# BATTERY_GESTION.net
KiCad netlist of a schematic drawn in Altium Designer
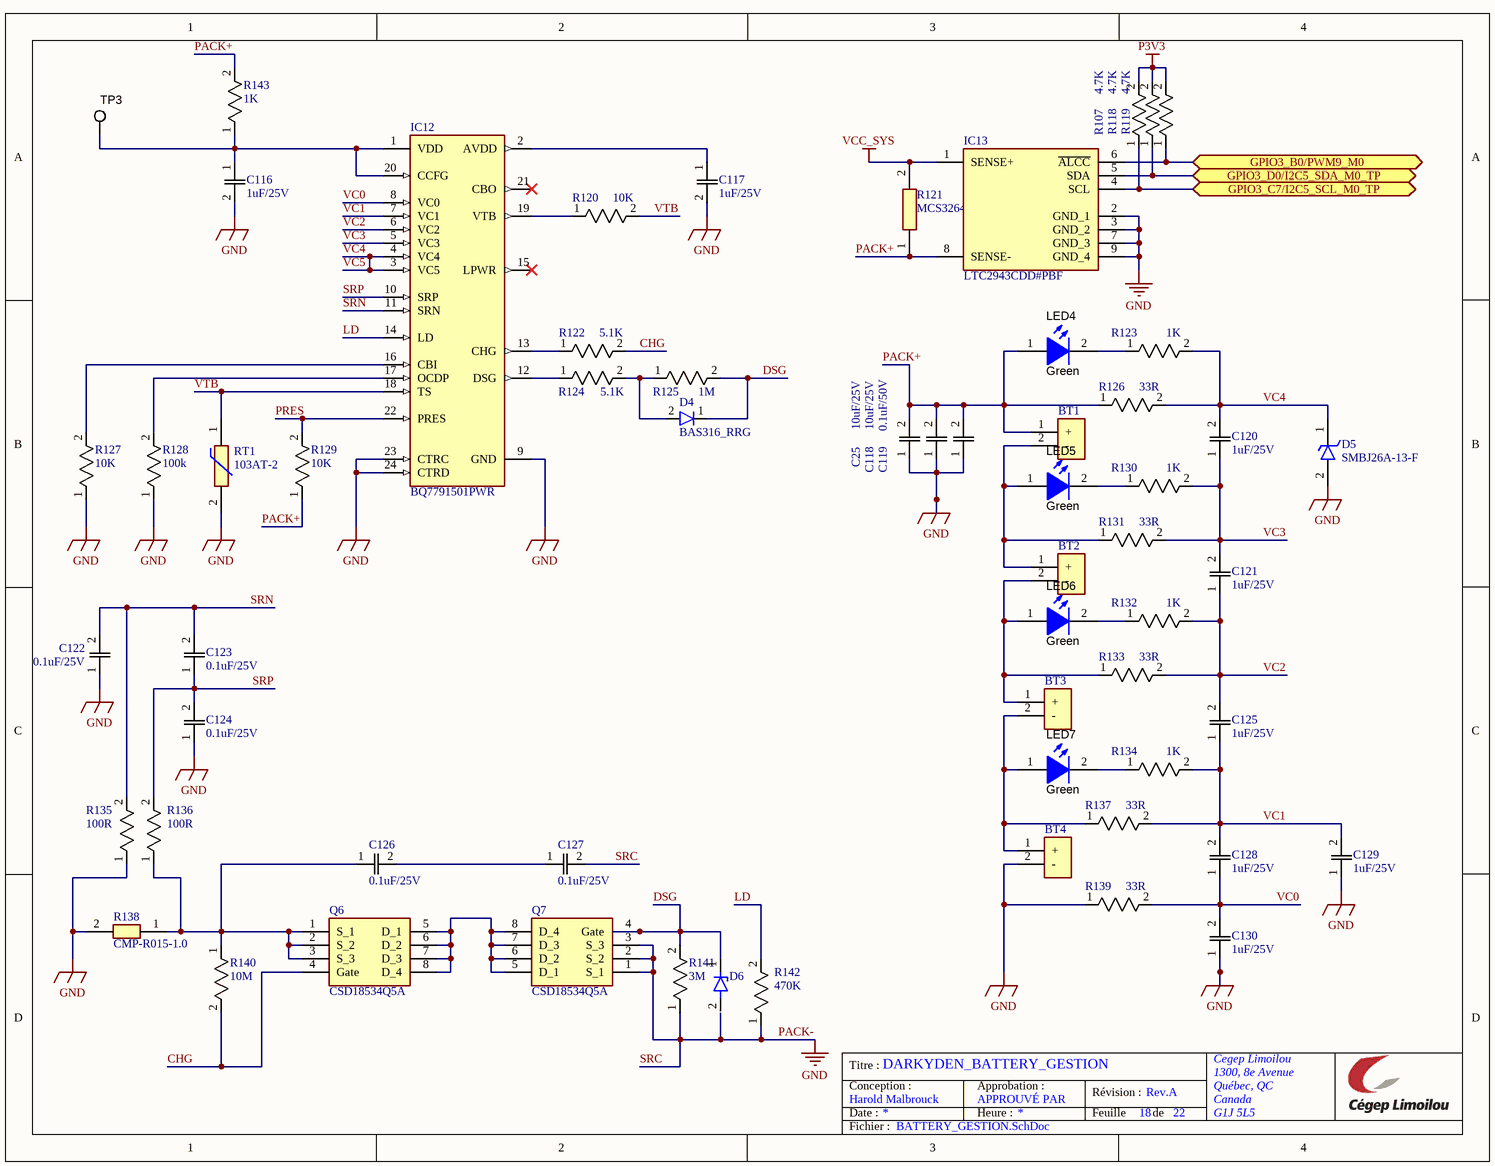
[diagram p0: BATTERY_GESTION.SchDoc]

(export (version "E")
  (design (tool "Eeschema 10.0.6"))
  (components
    (comp (ref "BT1")
      (value "0530480210")
      (footprint "SamacSys:SHDRRA2W35P0X125_1X2_425X550X350P")
      (description "Connector")
      (libsource (lib "SamacSys") (part "Header 1.25MM"))
    )
    (comp (ref "BT2")
      (value "0530480210")
      (footprint "SamacSys:SHDRRA2W35P0X125_1X2_425X550X350P")
      (description "Connector")
      (libsource (lib "SamacSys") (part "Header 1.25MM"))
    )
    (comp (ref "BT3")
      (value "0530480210")
      (footprint "SamacSys:SHDRRA2W35P0X125_1X2_425X550X350P")
      (description "Connector")
      (libsource (lib "SamacSys") (part "Header 1.25MM"))
    )
    (comp (ref "BT4")
      (value "0530480210")
      (footprint "SamacSys:SHDRRA2W35P0X125_1X2_425X550X350P")
      (description "Connector")
      (libsource (lib "SamacSys") (part "Header 1.25MM"))
    )
    (comp (ref "C25")
      (value "10uF/25V")
      (footprint "CAPC220145_88N_KEM")
      (description "10uF / 25 VDC, +85degC, X5R Dielec, +/-10% ¦ KEMET C0805C106K3PACTU 0805")
      (fields
        (field (name "MANUFACTURER") "KEMET")
        (field (name "MANUFACTURER PART NUMBER") "C0805C106K3PACTU")
      )
      (libsource (lib "C0805C106K3PACTU") (part "C0805C106K3PACTU"))
    )
    (comp (ref "C116")
      (value "1uF/25V")
      (footprint "SamacSys:C0805")
      (description "Ceramic capacitor, 1 µF, 25 V (DC), ±10 %, SMD 0805, X7R, C0805C105K3RAC7800")
      (fields
        (field (name "MANUFACTURER_PART_NUMBER") "C0805C105K3RACTU")
        (field (name "MOUSER PART NUMBER") "80-C0805C105K3R")
      )
      (libsource (lib "SamacSys") (part "C0805C105K3RACTU"))
    )
    (comp (ref "C117")
      (value "1uF/25V")
      (footprint "SamacSys:C0805")
      (description "Ceramic capacitor, 1 µF, 25 V (DC), ±10 %, SMD 0805, X7R, C0805C105K3RAC7800")
      (fields
        (field (name "MANUFACTURER_PART_NUMBER") "C0805C105K3RACTU")
        (field (name "MOUSER PART NUMBER") "80-C0805C105K3R")
      )
      (libsource (lib "SamacSys") (part "C0805C105K3RACTU"))
    )
    (comp (ref "C118")
      (value "10uF/25V")
      (footprint "CAPC220145_88N_KEM")
      (description "10uF / 25 VDC, +85degC, X5R Dielec, +/-10% ¦ KEMET C0805C106K3PACTU 0805")
      (fields
        (field (name "MANUFACTURER") "KEMET")
        (field (name "MANUFACTURER PART NUMBER") "C0805C106K3PACTU")
      )
      (libsource (lib "C0805C106K3PACTU") (part "C0805C106K3PACTU"))
    )
    (comp (ref "C119")
      (value "0.1uF/50V")
      (footprint "SamacSys:C0805")
      (description "0.1uF/50V X7R 10% 0805 Multilayer Ceramic Capacitors Mlcc Smd/Smt Rohs")
      (fields
        (field (name "MANUFACTURER_PART_NUMBER") "C0805C104K5RACTU")
        (field (name "MOUSER PART NUMBER") "80-C0805C104K5R")
      )
      (libsource (lib "SamacSys") (part "C0805C104K5RACTU"))
    )
    (comp (ref "C120")
      (value "1uF/25V")
      (footprint "SamacSys:C0805")
      (description "Ceramic capacitor, 1 µF, 25 V (DC), ±10 %, SMD 0805, X7R, C0805C105K3RAC7800")
      (fields
        (field (name "MANUFACTURER_PART_NUMBER") "C0805C105K3RACTU")
        (field (name "MOUSER PART NUMBER") "80-C0805C105K3R")
      )
      (libsource (lib "SamacSys") (part "C0805C105K3RACTU"))
    )
    (comp (ref "C121")
      (value "1uF/25V")
      (footprint "SamacSys:C0805")
      (description "Ceramic capacitor, 1 µF, 25 V (DC), ±10 %, SMD 0805, X7R, C0805C105K3RAC7800")
      (fields
        (field (name "MANUFACTURER_PART_NUMBER") "C0805C105K3RACTU")
        (field (name "MOUSER PART NUMBER") "80-C0805C105K3R")
      )
      (libsource (lib "SamacSys") (part "C0805C105K3RACTU"))
    )
    (comp (ref "C122")
      (value "0.1uF/25V")
      (footprint "CAPC220145_88N_KEM")
      (description "0.1uF 25V X7R 10% SMD 0805 125C Plastic T/R")
      (fields
        (field (name "MANUFACTURER") "KEMET")
        (field (name "MANUFACTURER PART NUMBER") "C0805C104K3RACTU")
      )
      (libsource (lib "C0805C104K3RACTU") (part "C0805C104K3RACTU"))
    )
    (comp (ref "C123")
      (value "0.1uF/25V")
      (footprint "CAPC220145_88N_KEM")
      (description "0.1uF 25V X7R 10% SMD 0805 125C Plastic T/R")
      (fields
        (field (name "MANUFACTURER") "KEMET")
        (field (name "MANUFACTURER PART NUMBER") "C0805C104K3RACTU")
      )
      (libsource (lib "C0805C104K3RACTU") (part "C0805C104K3RACTU"))
    )
    (comp (ref "C124")
      (value "0.1uF/25V")
      (footprint "CAPC220145_88N_KEM")
      (description "0.1uF 25V X7R 10% SMD 0805 125C Plastic T/R")
      (fields
        (field (name "MANUFACTURER") "KEMET")
        (field (name "MANUFACTURER PART NUMBER") "C0805C104K3RACTU")
      )
      (libsource (lib "C0805C104K3RACTU") (part "C0805C104K3RACTU"))
    )
    (comp (ref "C125")
      (value "1uF/25V")
      (footprint "SamacSys:C0805")
      (description "Ceramic capacitor, 1 µF, 25 V (DC), ±10 %, SMD 0805, X7R, C0805C105K3RAC7800")
      (fields
        (field (name "MANUFACTURER_PART_NUMBER") "C0805C105K3RACTU")
        (field (name "MOUSER PART NUMBER") "80-C0805C105K3R")
      )
      (libsource (lib "SamacSys") (part "C0805C105K3RACTU"))
    )
    (comp (ref "C126")
      (value "0.1uF/25V")
      (footprint "CAPC220145_88N_KEM")
      (description "0.1uF 25V X7R 10% SMD 0805 125C Plastic T/R")
      (fields
        (field (name "MANUFACTURER") "KEMET")
        (field (name "MANUFACTURER PART NUMBER") "C0805C104K3RACTU")
      )
      (libsource (lib "C0805C104K3RACTU") (part "C0805C104K3RACTU"))
    )
    (comp (ref "C127")
      (value "0.1uF/25V")
      (footprint "CAPC220145_88N_KEM")
      (description "0.1uF 25V X7R 10% SMD 0805 125C Plastic T/R")
      (fields
        (field (name "MANUFACTURER") "KEMET")
        (field (name "MANUFACTURER PART NUMBER") "C0805C104K3RACTU")
      )
      (libsource (lib "C0805C104K3RACTU") (part "C0805C104K3RACTU"))
    )
    (comp (ref "C128")
      (value "1uF/25V")
      (footprint "SamacSys:C0805")
      (description "Ceramic capacitor, 1 µF, 25 V (DC), ±10 %, SMD 0805, X7R, C0805C105K3RAC7800")
      (fields
        (field (name "MANUFACTURER_PART_NUMBER") "C0805C105K3RACTU")
        (field (name "MOUSER PART NUMBER") "80-C0805C105K3R")
      )
      (libsource (lib "SamacSys") (part "C0805C105K3RACTU"))
    )
    (comp (ref "C129")
      (value "1uF/25V")
      (footprint "SamacSys:C0805")
      (description "Ceramic capacitor, 1 µF, 25 V (DC), ±10 %, SMD 0805, X7R, C0805C105K3RAC7800")
      (fields
        (field (name "MANUFACTURER_PART_NUMBER") "C0805C105K3RACTU")
        (field (name "MOUSER PART NUMBER") "80-C0805C105K3R")
      )
      (libsource (lib "SamacSys") (part "C0805C105K3RACTU"))
    )
    (comp (ref "C130")
      (value "1uF/25V")
      (footprint "SamacSys:C0805")
      (description "Ceramic capacitor, 1 µF, 25 V (DC), ±10 %, SMD 0805, X7R, C0805C105K3RAC7800")
      (fields
        (field (name "MANUFACTURER_PART_NUMBER") "C0805C105K3RACTU")
        (field (name "MOUSER PART NUMBER") "80-C0805C105K3R")
      )
      (libsource (lib "SamacSys") (part "C0805C105K3RACTU"))
    )
    (comp (ref "D4")
      (value "BAS316_RRG")
      (footprint "SamacSys:BAS316RRG")
      (description "Rectifier Diode Small Signal Switching 0.25A 4ns 2-Pin SOD-323 T/R")
      (fields
        (field (name "MANUFACTURER_PART_NUMBER") "BAS316 RRG")
        (field (name "MOUSER PART NUMBER") "821-BAS316RRG")
      )
      (libsource (lib "SamacSys") (part "BAS316_RRG"))
    )
    (comp (ref "D5")
      (value "SMBJ26A-13-F")
      (footprint "SamacSys:DIOM5336X250N")
      (description "TVS DIODE 26VWM 42.1VC SMB")
      (fields (field (name "MOUSER PART NUMBER") "621-SMBJ26A-13-F"))
      (libsource (lib "SamacSys") (part "SMBJ26A-13-F"))
    )
    (comp (ref "D6")
      (value "MMSZ5248B-7-F")
      (footprint "SamacSys:SOD3716X115N")
      (description "Zener Diode 18 V 500 mW ±5% Surface Mount SOD-123")
      (libsource (lib "SamacSys") (part "MMSZ5248B-7-F"))
    )
    (comp (ref "IC12")
      (value "BQ7791501PWR")
      (footprint "SamacSys:SOP65P640X120-24N")
      (description "/Polymer 3~5 TSSOP-24 Battery Management ICs ROHS")
      (fields
        (field (name "MOUSER PART NUMBER") "595-BQ7791501PWR")
        (field (name "MANUFACTURER") "Texas Instruments")
      )
      (libsource (lib "SamacSys") (part "BQ7791501PWR"))
    )
    (comp (ref "IC13")
      (value "LTC2943CDD#PBF")
      (footprint "SamacSys:SON50P300X300X80-9N-D")
      (description "LTC2943 - Multicell Battery Gas Gauge with Temperature, Voltage and Current Measurement")
      (fields
        (field (name "MOUSER PART NUMBER") "584-LTC2943CDD#PBF")
        (field (name "MANUFACTURER") "Analog Devices / Linear Technology")
      )
      (libsource (lib "SamacSys") (part "LTC2943CDD#PBF"))
    )
    (comp (ref "LED4")
      (value "Green")
      (footprint "LED_LTST-C190")
      (description "LED, Green, SMD")
      (fields (field (name "MANUFACTURER") "Lite-On") (field (name "PARTNUMBER") "LTST-C190GKT"))
      (libsource (lib "texas_instrument_power") (part "LED_Gr_SMD"))
    )
    (comp (ref "LED5")
      (value "Green")
      (footprint "LED_LTST-C190")
      (description "LED, Green, SMD")
      (fields (field (name "MANUFACTURER") "Lite-On") (field (name "PARTNUMBER") "LTST-C190GKT"))
      (libsource (lib "texas_instrument_power") (part "LED_Gr_SMD"))
    )
    (comp (ref "LED6")
      (value "Green")
      (footprint "LED_LTST-C190")
      (description "LED, Green, SMD")
      (fields (field (name "MANUFACTURER") "Lite-On") (field (name "PARTNUMBER") "LTST-C190GKT"))
      (libsource (lib "texas_instrument_power") (part "LED_Gr_SMD"))
    )
    (comp (ref "LED7")
      (value "Green")
      (footprint "LED_LTST-C190")
      (description "LED, Green, SMD")
      (fields (field (name "MANUFACTURER") "Lite-On") (field (name "PARTNUMBER") "LTST-C190GKT"))
      (libsource (lib "texas_instrument_power") (part "LED_Gr_SMD"))
    )
    (comp (ref "Q6")
      (value "CSD18534Q5A")
      (footprint "SamacSys:Q5A")
      (description "MOSFET N-Channel 60 V 13A (Ta), 50A (Tc) 3.1W (Ta), 77W (Tc) Surface Mount 8-VSONP (5x6)")
      (fields (field (name "MOUSER PART NUMBER") "595-CSD18534Q5A"))
      (libsource (lib "") (part "CSD18534Q5A_1"))
    )
    (comp (ref "Q7")
      (value "CSD18534Q5A")
      (footprint "SamacSys:Q5A")
      (description "MOSFET N-Channel 60 V 13A (Ta), 50A (Tc) 3.1W (Ta), 77W (Tc) Surface Mount 8-VSONP (5x6)")
      (fields (field (name "MOUSER PART NUMBER") "595-CSD18534Q5A"))
      (libsource (lib "SamacSys") (part "CSD18534Q5A"))
    )
    (comp (ref "R107")
      (value "4.7K")
      (footprint "RC0603N_PAN")
      (description "Res Thin Film 0603 4.7K Ohm 0.1% 0.1W ±25ppm/°C Molded SMD Punched Carrier T/R")
      (fields
        (field (name "MANUFACTURER") "Panasonic")
        (field (name "MANUFACTURER PART NUMBER") "ERA-3AEB472V")
      )
      (libsource (lib "ERA-3AEB472V") (part "ERA-3AEB472V"))
    )
    (comp (ref "R118")
      (value "4.7K")
      (footprint "RC0603N_PAN")
      (description "Res Thin Film 0603 4.7K Ohm 0.1% 0.1W ±25ppm/°C Molded SMD Punched Carrier T/R")
      (fields
        (field (name "MANUFACTURER") "Panasonic")
        (field (name "MANUFACTURER PART NUMBER") "ERA-3AEB472V")
      )
      (libsource (lib "ERA-3AEB472V") (part "ERA-3AEB472V"))
    )
    (comp (ref "R119")
      (value "4.7K")
      (footprint "RC0603N_PAN")
      (description "Res Thin Film 0603 4.7K Ohm 0.1% 0.1W ±25ppm/°C Molded SMD Punched Carrier T/R")
      (fields
        (field (name "MANUFACTURER") "Panasonic")
        (field (name "MANUFACTURER PART NUMBER") "ERA-3AEB472V")
      )
      (libsource (lib "ERA-3AEB472V") (part "ERA-3AEB472V"))
    )
    (comp (ref "R120")
      (value "10K")
      (footprint "SamacSys:ERJ3EKF1000V")
      (description "10K Ohm 5% Res Thick Film 0603  0.1W(1/10W) ±200ppm/C Pad SMD Automotive T/R")
      (fields
        (field (name "MANUFACTURER_PART_NUMBER") "ERJ-3GEYJ103V")
        (field (name "MOUSER PART NUMBER") "667-ERJ-3GEYJ103V")
      )
      (libsource (lib "SamacSys") (part "ERJ-3GEYJ103V"))
    )
    (comp (ref "R121")
      (value "MCS3264R010FER")
      (footprint "SamacSys:RESC6432X62N")
      (description "Res Metal Alloy 2512 0.01 Ohm 1% 2W 50ppm/ C Molded SMD T/R")
      (fields (field (name "MOUSER PART NUMBER") "588-MCS3264R010FER") (field (name "MANUFACTURER") "Ohmite"))
      (libsource (lib "SamacSys") (part "MCS3264R010FER"))
    )
    (comp (ref "R122")
      (value "5.1K")
      (footprint "SamacSys:ERA3AEB101V")
      (description "5.1K Ohm 0.05% 0.1W ±10ppm/°C Molded Res Thin Film 0603 SMD Punched Carrier T/R")
      (fields
        (field (name "MANUFACTURER_PART_NUMBER") "ERA-3ARW512V")
        (field (name "MOUSER PART NUMBER") "667-ERA-3ARW512V")
      )
      (libsource (lib "SamacSys") (part "ERA-3ARW512V"))
    )
    (comp (ref "R123")
      (value "1K")
      (footprint "SamacSys:RESC1608X55N")
      (description "1K Ohm 1% 1/10W Res Thick Film 0603 ±100ppm/°C Molded SMD Punched Carrier T/R")
      (fields
        (field (name "MANUFACTURER_PART_NUMBER") "ERJ-3EKF1001V")
        (field (name "MOUSER PART NUMBER") "667-ERJ-3EKF1001V")
      )
      (libsource (lib "SamacSys") (part "ERJ-3EKF1001V"))
    )
    (comp (ref "R124")
      (value "5.1K")
      (footprint "SamacSys:ERA3AEB101V")
      (description "5.1K Ohm 0.05% 0.1W ±10ppm/°C Molded Res Thin Film 0603 SMD Punched Carrier T/R")
      (fields
        (field (name "MANUFACTURER_PART_NUMBER") "ERA-3ARW512V")
        (field (name "MOUSER PART NUMBER") "667-ERA-3ARW512V")
      )
      (libsource (lib "SamacSys") (part "ERA-3ARW512V"))
    )
    (comp (ref "R125")
      (value "1M")
      (footprint "SamacSys:ERJ3EKF1000V")
      (description "1M Ohm Res Thick Film 0603 5% 0.1W(1/10W) +/-200ppm/ßC SMD Automotive T/R")
      (fields
        (field (name "MANUFACTURER_PART_NUMBER") "ERJ-3GEYJ105V")
        (field (name "MOUSER PART NUMBER") "667-ERJ-3GEYJ105V")
      )
      (libsource (lib "SamacSys") (part "ERJ-3GEYJ105V"))
    )
    (comp (ref "R126")
      (value "33R")
      (footprint "RC0603N_PAN")
      (description "Res Thick Film 0603 33 Ohm 1% 0.1W ±100ppm/°C Molded SMD Punched Carrier T/R")
      (fields
        (field (name "MANUFACTURER") "Panasonic")
        (field (name "MANUFACTURER PART NUMBER") "ERJ-3EKF33R0V")
      )
      (libsource (lib "ERJ-3EKF33R0V") (part "ERJ-3EKF33R0V"))
    )
    (comp (ref "R127")
      (value "10K")
      (footprint "SamacSys:ERJ3EKF1000V")
      (description "10K Ohm 5% Res Thick Film 0603  0.1W(1/10W) ±200ppm/C Pad SMD Automotive T/R")
      (fields
        (field (name "MANUFACTURER_PART_NUMBER") "ERJ-3GEYJ103V")
        (field (name "MOUSER PART NUMBER") "667-ERJ-3GEYJ103V")
      )
      (libsource (lib "SamacSys") (part "ERJ-3GEYJ103V"))
    )
    (comp (ref "R128")
      (value "100k")
      (footprint "SamacSys:ERJ3EKF1000V")
      (description "100K Ohm 5%  Res Thick Film 0603 1/10W +/-200ppm/ßC Molded SMD Punched Carrier T/R")
      (fields
        (field (name "MANUFACTURER_PART_NUMBER") "ERJ-3GEYJ104V")
        (field (name "MOUSER PART NUMBER") "667-ERJ-3GEYJ104V")
      )
      (libsource (lib "SamacSys") (part "ERJ-3GEYJ104V"))
    )
    (comp (ref "R129")
      (value "10K")
      (footprint "SamacSys:ERJ3EKF1000V")
      (description "10K Ohm 5% Res Thick Film 0603  0.1W(1/10W) ±200ppm/C Pad SMD Automotive T/R")
      (fields
        (field (name "MANUFACTURER_PART_NUMBER") "ERJ-3GEYJ103V")
        (field (name "MOUSER PART NUMBER") "667-ERJ-3GEYJ103V")
      )
      (libsource (lib "SamacSys") (part "ERJ-3GEYJ103V"))
    )
    (comp (ref "R130")
      (value "1K")
      (footprint "SamacSys:RESC1608X55N")
      (description "1K Ohm 1% 1/10W Res Thick Film 0603 ±100ppm/°C Molded SMD Punched Carrier T/R")
      (fields
        (field (name "MANUFACTURER_PART_NUMBER") "ERJ-3EKF1001V")
        (field (name "MOUSER PART NUMBER") "667-ERJ-3EKF1001V")
      )
      (libsource (lib "SamacSys") (part "ERJ-3EKF1001V"))
    )
    (comp (ref "R131")
      (value "33R")
      (footprint "RC0603N_PAN")
      (description "Res Thick Film 0603 33 Ohm 1% 0.1W ±100ppm/°C Molded SMD Punched Carrier T/R")
      (fields
        (field (name "MANUFACTURER") "Panasonic")
        (field (name "MANUFACTURER PART NUMBER") "ERJ-3EKF33R0V")
      )
      (libsource (lib "ERJ-3EKF33R0V") (part "ERJ-3EKF33R0V"))
    )
    (comp (ref "R132")
      (value "1K")
      (footprint "SamacSys:RESC1608X55N")
      (description "1K Ohm 1% 1/10W Res Thick Film 0603 ±100ppm/°C Molded SMD Punched Carrier T/R")
      (fields
        (field (name "MANUFACTURER_PART_NUMBER") "ERJ-3EKF1001V")
        (field (name "MOUSER PART NUMBER") "667-ERJ-3EKF1001V")
      )
      (libsource (lib "SamacSys") (part "ERJ-3EKF1001V"))
    )
    (comp (ref "R133")
      (value "33R")
      (footprint "RC0603N_PAN")
      (description "Res Thick Film 0603 33 Ohm 1% 0.1W ±100ppm/°C Molded SMD Punched Carrier T/R")
      (fields
        (field (name "MANUFACTURER") "Panasonic")
        (field (name "MANUFACTURER PART NUMBER") "ERJ-3EKF33R0V")
      )
      (libsource (lib "ERJ-3EKF33R0V") (part "ERJ-3EKF33R0V"))
    )
    (comp (ref "R134")
      (value "1K")
      (footprint "SamacSys:RESC1608X55N")
      (description "1K Ohm 1% 1/10W Res Thick Film 0603 ±100ppm/°C Molded SMD Punched Carrier T/R")
      (fields
        (field (name "MANUFACTURER_PART_NUMBER") "ERJ-3EKF1001V")
        (field (name "MOUSER PART NUMBER") "667-ERJ-3EKF1001V")
      )
      (libsource (lib "SamacSys") (part "ERJ-3EKF1001V"))
    )
    (comp (ref "R135")
      (value "100R")
      (footprint "SamacSys:RESC1608X55N")
      (description "100 Ohm 1% 1/10W 0603 ±100ppm/°C Molded SMD Punched Carrier T/R")
      (fields
        (field (name "MANUFACTURER_PART_NUMBER") "ERJ-3EKF1000V")
        (field (name "MOUSER PART NUMBER") "667-ERJ-3EKF1000V")
      )
      (libsource (lib "SamacSys") (part "ERJ-3EKF1000V"))
    )
    (comp (ref "R136")
      (value "100R")
      (footprint "SamacSys:RESC1608X55N")
      (description "100 Ohm 1% 1/10W 0603 ±100ppm/°C Molded SMD Punched Carrier T/R")
      (fields
        (field (name "MANUFACTURER_PART_NUMBER") "ERJ-3EKF1000V")
        (field (name "MOUSER PART NUMBER") "667-ERJ-3EKF1000V")
      )
      (libsource (lib "SamacSys") (part "ERJ-3EKF1000V"))
    )
    (comp (ref "R137")
      (value "33R")
      (footprint "RC0603N_PAN")
      (description "Res Thick Film 0603 33 Ohm 1% 0.1W ±100ppm/°C Molded SMD Punched Carrier T/R")
      (fields
        (field (name "MANUFACTURER") "Panasonic")
        (field (name "MANUFACTURER PART NUMBER") "ERJ-3EKF33R0V")
      )
      (libsource (lib "ERJ-3EKF33R0V") (part "ERJ-3EKF33R0V"))
    )
    (comp (ref "R138")
      (value "CMP-R015-1.0")
      (footprint "SamacSys:RESC5025X70N")
      (description "Resistor ISA-PLAN 2010 R015 1%")
      (fields
        (field (name "MANUFACTURER_PART_NUMBER") "CRCW20100000Z0EFHP")
        (field (name "MOUSER PART NUMBER") "71-CRCW20100000Z0EFH")
      )
      (libsource (lib "SamacSys") (part "Resistor 2010"))
    )
    (comp (ref "R139")
      (value "33R")
      (footprint "RC0603N_PAN")
      (description "Res Thick Film 0603 33 Ohm 1% 0.1W ±100ppm/°C Molded SMD Punched Carrier T/R")
      (fields
        (field (name "MANUFACTURER") "Panasonic")
        (field (name "MANUFACTURER PART NUMBER") "ERJ-3EKF33R0V")
      )
      (libsource (lib "ERJ-3EKF33R0V") (part "ERJ-3EKF33R0V"))
    )
    (comp (ref "R140")
      (value "10M")
      (footprint "SamacSys:ERJS03J155V")
      (description "10Mohm 5%  SMD 0603   Anti-Sulfur AEC-Q200")
      (fields
        (field (name "MANUFACTURER_PART_NUMBER") "ERJ-U03J106V")
        (field (name "MOUSER PART NUMBER") "667-ERJ-U03J106V")
      )
      (libsource (lib "SamacSys") (part "ERJ-U03J106V"))
    )
    (comp (ref "R141")
      (value "3M")
      (footprint "SamacSys:ERJ3EKF1000V")
      (description "3M Ohm 5% 1/10W Res Thick Film 0603 -400ppm/ to 150ppm¦")
      (fields
        (field (name "MANUFACTURER_PART_NUMBER") "ERJ-3GEYJ305V")
        (field (name "MOUSER PART NUMBER") "667-ERJ-3GEYJ305V")
      )
      (libsource (lib "SamacSys") (part "ERJ-3GEYJ305V"))
    )
    (comp (ref "R142")
      (value "470K")
      (footprint "SamacSys:RESC1608X55N")
      (description "470K Ohm 1% 0.1W  Res Thick Film 0603 ±100ppm/°C Molded SMD Punched Carrier T/R")
      (fields
        (field (name "MANUFACTURER_PART_NUMBER") "ERJ-3EKF4703V")
        (field (name "MOUSER PART NUMBER") "667-ERJ-3EKF4703V")
      )
      (libsource (lib "SamacSys") (part "ERJ-3EKF4703V"))
    )
    (comp (ref "R143")
      (value "1K")
      (footprint "SamacSys:RESC1608X55N")
      (description "1K Ohm 1% 1/10W Res Thick Film 0603 ±100ppm/°C Molded SMD Punched Carrier T/R")
      (fields
        (field (name "MANUFACTURER_PART_NUMBER") "ERJ-3EKF1001V")
        (field (name "MOUSER PART NUMBER") "667-ERJ-3EKF1001V")
      )
      (libsource (lib "SamacSys") (part "ERJ-3EKF1001V"))
    )
    (comp (ref "RT1")
      (value "103AT-2")
      (footprint "SamacSys:103AT2")
      (description "NTC Thermistor, 10000ohm, Through Hole Mount")
      (fields (field (name "MOUSER PART NUMBER") "954-103AT-2") (field (name "MANUFACTURER") "Semitec"))
      (libsource (lib "SamacSys") (part "103AT-2"))
    )
    (comp (ref "TP3")
      (value "5016")
      (footprint "Testpoint_Keystone_Compact")
      (description "Test Point, Compact, SMT")
      (fields (field (name "MANUFACTURER") "Keystone") (field (name "PUBLISHER") "Texas Instruments"))
      (libsource (lib "texas_instrument_power") (part "TEST_POINT1"))
    )
  )
  (nets
    (net (code "1") (name "/CHG") (class "Default")
      (node (ref "Q6") (pin "4") (pinfunction "Gate_4") (pintype "passive"))
      (node (ref "R122") (pin "2") (pinfunction "2_2") (pintype "passive"))
      (node (ref "R140") (pin "2") (pinfunction "2_2") (pintype "passive"))
    )
    (net (code "2") (name "/DSG") (class "Default")
      (node (ref "D4") (pin "1") (pinfunction "K_1") (pintype "passive"))
      (node (ref "D6") (pin "1") (pinfunction "K_1") (pintype "passive"))
      (node (ref "Q7") (pin "4") (pinfunction "Gate_4") (pintype "passive"))
      (node (ref "R125") (pin "2") (pinfunction "2_2") (pintype "passive"))
      (node (ref "R141") (pin "2") (pinfunction "2_2") (pintype "passive"))
    )
    (net (code "3") (name "/GPIO3_B0{slash}PWM9_M0") (class "Default")
      (node (ref "IC13") (pin "6") (pinfunction "~{ALCC}_6") (pintype "passive"))
      (node (ref "R119") (pin "1") (pinfunction "1_1") (pintype "passive"))
    )
    (net (code "4") (name "/GPIO3_C7{slash}I2C5_SCL_M0_TP") (class "Default")
      (node (ref "IC13") (pin "4") (pinfunction "SCL_4") (pintype "passive"))
      (node (ref "R107") (pin "1") (pinfunction "1_1") (pintype "passive"))
    )
    (net (code "5") (name "/GPIO3_D0{slash}I2C5_SDA_M0_TP") (class "Default")
      (node (ref "IC13") (pin "5") (pinfunction "SDA_5") (pintype "passive"))
      (node (ref "R118") (pin "1") (pinfunction "1_1") (pintype "passive"))
    )
    (net (code "6") (name "/LD") (class "Default")
      (node (ref "IC12") (pin "14") (pinfunction "LD_14") (pintype "input"))
      (node (ref "R142") (pin "2") (pinfunction "2_2") (pintype "passive"))
    )
    (net (code "7") (name "/PACK+") (class "Default")
      (node (ref "BT1") (pin "1") (pinfunction "+_1") (pintype "passive"))
      (node (ref "C118") (pin "2") (pinfunction "2_2") (pintype "passive"))
      (node (ref "C119") (pin "2") (pinfunction "2_2") (pintype "passive"))
      (node (ref "C25") (pin "2") (pinfunction "2_2") (pintype "passive"))
      (node (ref "IC13") (pin "8") (pinfunction "SENSE-_8") (pintype "passive"))
      (node (ref "LED4") (pin "1") (pinfunction "A_1") (pintype "passive"))
      (node (ref "R121") (pin "1") (pinfunction "1_1") (pintype "passive"))
      (node (ref "R126") (pin "1") (pinfunction "1_1") (pintype "passive"))
      (node (ref "R129") (pin "1") (pinfunction "1_1") (pintype "passive"))
      (node (ref "R143") (pin "2") (pinfunction "2_2") (pintype "passive"))
    )
    (net (code "8") (name "/PRES") (class "Default")
      (node (ref "IC12") (pin "22") (pinfunction "PRES_22") (pintype "input"))
      (node (ref "R129") (pin "2") (pinfunction "2_2") (pintype "passive"))
    )
    (net (code "9") (name "/SRN") (class "Default")
      (node (ref "C122") (pin "2") (pinfunction "2_2") (pintype "passive"))
      (node (ref "C123") (pin "2") (pinfunction "2_2") (pintype "passive"))
      (node (ref "IC12") (pin "11") (pinfunction "SRN_11") (pintype "input"))
      (node (ref "R135") (pin "2") (pinfunction "2_2") (pintype "passive"))
    )
    (net (code "10") (name "/SRP") (class "Default")
      (node (ref "C123") (pin "1") (pinfunction "1_1") (pintype "passive"))
      (node (ref "C124") (pin "2") (pinfunction "2_2") (pintype "passive"))
      (node (ref "IC12") (pin "10") (pinfunction "SRP_10") (pintype "input"))
      (node (ref "R136") (pin "2") (pinfunction "2_2") (pintype "passive"))
    )
    (net (code "11") (name "/VC0") (class "Default")
      (node (ref "C128") (pin "1") (pinfunction "1_1") (pintype "passive"))
      (node (ref "C130") (pin "2") (pinfunction "2_2") (pintype "passive"))
      (node (ref "IC12") (pin "8") (pinfunction "VC0_8") (pintype "input"))
      (node (ref "R139") (pin "2") (pinfunction "2_2") (pintype "passive"))
    )
    (net (code "12") (name "/VC1") (class "Default")
      (node (ref "C125") (pin "1") (pinfunction "1_1") (pintype "passive"))
      (node (ref "C128") (pin "2") (pinfunction "2_2") (pintype "passive"))
      (node (ref "C129") (pin "2") (pinfunction "2_2") (pintype "passive"))
      (node (ref "IC12") (pin "7") (pinfunction "VC1_7") (pintype "input"))
      (node (ref "R134") (pin "2") (pinfunction "2_2") (pintype "passive"))
      (node (ref "R137") (pin "2") (pinfunction "2_2") (pintype "passive"))
    )
    (net (code "13") (name "/VC2") (class "Default")
      (node (ref "C121") (pin "1") (pinfunction "1_1") (pintype "passive"))
      (node (ref "C125") (pin "2") (pinfunction "2_2") (pintype "passive"))
      (node (ref "IC12") (pin "6") (pinfunction "VC2_6") (pintype "input"))
      (node (ref "R132") (pin "2") (pinfunction "2_2") (pintype "passive"))
      (node (ref "R133") (pin "2") (pinfunction "2_2") (pintype "passive"))
    )
    (net (code "14") (name "/VC3") (class "Default")
      (node (ref "C120") (pin "1") (pinfunction "1_1") (pintype "passive"))
      (node (ref "C121") (pin "2") (pinfunction "2_2") (pintype "passive"))
      (node (ref "IC12") (pin "5") (pinfunction "VC3_5") (pintype "input"))
      (node (ref "R130") (pin "2") (pinfunction "2_2") (pintype "passive"))
      (node (ref "R131") (pin "2") (pinfunction "2_2") (pintype "passive"))
    )
    (net (code "15") (name "/VC4") (class "Default")
      (node (ref "C120") (pin "2") (pinfunction "2_2") (pintype "passive"))
      (node (ref "D5") (pin "1") (pinfunction "K_1") (pintype "passive"))
      (node (ref "IC12") (pin "3") (pinfunction "VC5_3") (pintype "input"))
      (node (ref "IC12") (pin "4") (pinfunction "VC4_4") (pintype "input"))
      (node (ref "R123") (pin "2") (pinfunction "2_2") (pintype "passive"))
      (node (ref "R126") (pin "2") (pinfunction "2_2") (pintype "passive"))
    )
    (net (code "16") (name "/VTB") (class "Default")
      (node (ref "IC12") (pin "18") (pinfunction "TS_18") (pintype "input"))
      (node (ref "R120") (pin "2") (pinfunction "2_2") (pintype "passive"))
      (node (ref "RT1") (pin "1") (pinfunction "1_1") (pintype "passive"))
    )
    (net (code "17") (name "GND") (class "Default")
      (node (ref "BT4") (pin "2") (pinfunction "-_2") (pintype "passive"))
      (node (ref "C116") (pin "2") (pinfunction "2_2") (pintype "passive"))
      (node (ref "C117") (pin "2") (pinfunction "2_2") (pintype "passive"))
      (node (ref "C118") (pin "1") (pinfunction "1_1") (pintype "passive"))
      (node (ref "C119") (pin "1") (pinfunction "1_1") (pintype "passive"))
      (node (ref "C122") (pin "1") (pinfunction "1_1") (pintype "passive"))
      (node (ref "C124") (pin "1") (pinfunction "1_1") (pintype "passive"))
      (node (ref "C127") (pin "2") (pinfunction "2_2") (pintype "passive"))
      (node (ref "C129") (pin "1") (pinfunction "1_1") (pintype "passive"))
      (node (ref "C130") (pin "1") (pinfunction "1_1") (pintype "passive"))
      (node (ref "C25") (pin "1") (pinfunction "1_1") (pintype "passive"))
      (node (ref "D5") (pin "2") (pinfunction "A_2") (pintype "passive"))
      (node (ref "IC12") (pin "23") (pinfunction "CTRC_23") (pintype "input"))
      (node (ref "IC12") (pin "24") (pinfunction "CTRD_24") (pintype "input"))
      (node (ref "IC12") (pin "9") (pinfunction "GND_9") (pintype "passive"))
      (node (ref "IC13") (pin "2") (pinfunction "GND_1_2") (pintype "passive"))
      (node (ref "IC13") (pin "3") (pinfunction "GND_2_3") (pintype "passive"))
      (node (ref "IC13") (pin "7") (pinfunction "GND_3_7") (pintype "passive"))
      (node (ref "IC13") (pin "9") (pinfunction "GND_4_9") (pintype "passive"))
      (node (ref "Q7") (pin "1") (pinfunction "S_1_1") (pintype "passive"))
      (node (ref "Q7") (pin "2") (pinfunction "S_2_2") (pintype "passive"))
      (node (ref "Q7") (pin "3") (pinfunction "S_3_3") (pintype "passive"))
      (node (ref "R127") (pin "1") (pinfunction "1_1") (pintype "passive"))
      (node (ref "R128") (pin "1") (pinfunction "1_1") (pintype "passive"))
      (node (ref "R135") (pin "1") (pinfunction "1_1") (pintype "passive"))
      (node (ref "R138") (pin "2") (pinfunction "2_2") (pintype "passive"))
      (node (ref "R139") (pin "1") (pinfunction "1_1") (pintype "passive"))
      (node (ref "R141") (pin "1") (pinfunction "1_1") (pintype "passive"))
      (node (ref "R142") (pin "1") (pinfunction "1_1") (pintype "passive"))
      (node (ref "RT1") (pin "2") (pinfunction "2_2") (pintype "passive"))
    )
    (net (code "18") (name "Net-(BT1--)") (class "Default")
      (node (ref "BT1") (pin "2") (pinfunction "-_2") (pintype "passive"))
      (node (ref "BT2") (pin "1") (pinfunction "+_1") (pintype "passive"))
      (node (ref "LED5") (pin "1") (pinfunction "A_1") (pintype "passive"))
      (node (ref "R131") (pin "1") (pinfunction "1_1") (pintype "passive"))
    )
    (net (code "19") (name "Net-(BT2--)") (class "Default")
      (node (ref "BT2") (pin "2") (pinfunction "-_2") (pintype "passive"))
      (node (ref "BT3") (pin "1") (pinfunction "+_1") (pintype "passive"))
      (node (ref "LED6") (pin "1") (pinfunction "A_1") (pintype "passive"))
      (node (ref "R133") (pin "1") (pinfunction "1_1") (pintype "passive"))
    )
    (net (code "20") (name "Net-(BT3--)") (class "Default")
      (node (ref "BT3") (pin "2") (pinfunction "-_2") (pintype "passive"))
      (node (ref "BT4") (pin "1") (pinfunction "+_1") (pintype "passive"))
      (node (ref "LED7") (pin "1") (pinfunction "A_1") (pintype "passive"))
      (node (ref "R137") (pin "1") (pinfunction "1_1") (pintype "passive"))
    )
    (net (code "21") (name "Net-(C126-Pad2)") (class "Default")
      (node (ref "C126") (pin "2") (pinfunction "2_2") (pintype "passive"))
      (node (ref "C127") (pin "1") (pinfunction "1_1") (pintype "passive"))
    )
    (net (code "22") (name "Net-(D4-A)") (class "Default")
      (node (ref "D4") (pin "2") (pinfunction "A_2") (pintype "passive"))
      (node (ref "R124") (pin "2") (pinfunction "2_2") (pintype "passive"))
      (node (ref "R125") (pin "1") (pinfunction "1_1") (pintype "passive"))
    )
    (net (code "23") (name "Net-(IC12-AVDD)") (class "Default")
      (node (ref "C117") (pin "1") (pinfunction "1_1") (pintype "passive"))
      (node (ref "IC12") (pin "2") (pinfunction "AVDD_2") (pintype "output"))
    )
    (net (code "24") (name "Net-(IC12-CBI)") (class "Default")
      (node (ref "IC12") (pin "16") (pinfunction "CBI_16") (pintype "input"))
      (node (ref "R127") (pin "2") (pinfunction "2_2") (pintype "passive"))
    )
    (net (code "25") (name "Net-(IC12-CCFG)") (class "Default")
      (node (ref "C116") (pin "1") (pinfunction "1_1") (pintype "passive"))
      (node (ref "IC12") (pin "1") (pinfunction "VDD_1") (pintype "power_in"))
      (node (ref "IC12") (pin "20") (pinfunction "CCFG_20") (pintype "input"))
      (node (ref "R143") (pin "1") (pinfunction "1_1") (pintype "passive"))
      (node (ref "TP3") (pin "1") (pintype "passive"))
    )
    (net (code "26") (name "Net-(IC12-CHG)") (class "Default")
      (node (ref "IC12") (pin "13") (pinfunction "CHG_13") (pintype "output"))
      (node (ref "R122") (pin "1") (pinfunction "1_1") (pintype "passive"))
    )
    (net (code "27") (name "Net-(IC12-DSG)") (class "Default")
      (node (ref "IC12") (pin "12") (pinfunction "DSG_12") (pintype "output"))
      (node (ref "R124") (pin "1") (pinfunction "1_1") (pintype "passive"))
    )
    (net (code "28") (name "Net-(IC12-OCDP)") (class "Default")
      (node (ref "IC12") (pin "17") (pinfunction "OCDP_17") (pintype "input"))
      (node (ref "R128") (pin "2") (pinfunction "2_2") (pintype "passive"))
    )
    (net (code "29") (name "Net-(IC12-VTB)") (class "Default")
      (node (ref "IC12") (pin "19") (pinfunction "VTB_19") (pintype "output"))
      (node (ref "R120") (pin "1") (pinfunction "1_1") (pintype "passive"))
    )
    (net (code "30") (name "Net-(LED4-K)") (class "Default")
      (node (ref "LED4") (pin "2") (pinfunction "K_2") (pintype "passive"))
      (node (ref "R123") (pin "1") (pinfunction "1_1") (pintype "passive"))
    )
    (net (code "31") (name "Net-(LED5-K)") (class "Default")
      (node (ref "LED5") (pin "2") (pinfunction "K_2") (pintype "passive"))
      (node (ref "R130") (pin "1") (pinfunction "1_1") (pintype "passive"))
    )
    (net (code "32") (name "Net-(LED6-K)") (class "Default")
      (node (ref "LED6") (pin "2") (pinfunction "K_2") (pintype "passive"))
      (node (ref "R132") (pin "1") (pinfunction "1_1") (pintype "passive"))
    )
    (net (code "33") (name "Net-(LED7-K)") (class "Default")
      (node (ref "LED7") (pin "2") (pinfunction "K_2") (pintype "passive"))
      (node (ref "R134") (pin "1") (pinfunction "1_1") (pintype "passive"))
    )
    (net (code "34") (name "Net-(Q6-D_1)") (class "Default")
      (node (ref "Q6") (pin "5") (pinfunction "D_1_5") (pintype "passive"))
      (node (ref "Q6") (pin "6") (pinfunction "D_2_6") (pintype "passive"))
      (node (ref "Q6") (pin "7") (pinfunction "D_3_7") (pintype "passive"))
      (node (ref "Q6") (pin "8") (pinfunction "D_4_8") (pintype "passive"))
      (node (ref "Q7") (pin "5") (pinfunction "D_1_5") (pintype "passive"))
      (node (ref "Q7") (pin "6") (pinfunction "D_2_6") (pintype "passive"))
      (node (ref "Q7") (pin "7") (pinfunction "D_3_7") (pintype "passive"))
      (node (ref "Q7") (pin "8") (pinfunction "D_4_8") (pintype "passive"))
    )
    (net (code "35") (name "Net-(Q6-S_1)") (class "Default")
      (node (ref "C126") (pin "1") (pinfunction "1_1") (pintype "passive"))
      (node (ref "Q6") (pin "1") (pinfunction "S_1_1") (pintype "passive"))
      (node (ref "Q6") (pin "2") (pinfunction "S_2_2") (pintype "passive"))
      (node (ref "Q6") (pin "3") (pinfunction "S_3_3") (pintype "passive"))
      (node (ref "R136") (pin "1") (pinfunction "1_1") (pintype "passive"))
      (node (ref "R138") (pin "1") (pinfunction "1_1") (pintype "passive"))
      (node (ref "R140") (pin "1") (pinfunction "1_1") (pintype "passive"))
    )
    (net (code "36") (name "P3V3") (class "Default")
      (node (ref "R107") (pin "2") (pinfunction "2_2") (pintype "passive"))
      (node (ref "R118") (pin "2") (pinfunction "2_2") (pintype "passive"))
      (node (ref "R119") (pin "2") (pinfunction "2_2") (pintype "passive"))
    )
    (net (code "37") (name "VCC_SYS") (class "Default")
      (node (ref "IC13") (pin "1") (pinfunction "SENSE+_1") (pintype "passive"))
      (node (ref "R121") (pin "2") (pinfunction "2_2") (pintype "passive"))
    )
    (net (code "38") (name "unconnected-(D6-A-Pad2)") (class "Default")
      (node (ref "D6") (pin "2") (pinfunction "A_2") (pintype "passive"))
    )
    (net (code "39") (name "unconnected-(IC12-CBO-Pad21)") (class "Default")
      (node (ref "IC12") (pin "21") (pinfunction "CBO_21") (pintype "output+no_connect"))
    )
    (net (code "40") (name "unconnected-(IC12-LPWR-Pad15)") (class "Default")
      (node (ref "IC12") (pin "15") (pinfunction "LPWR_15") (pintype "output+no_connect"))
    )
  )
)
